# SubHarmonics_Main_Board_v2.net
KiCad netlist of a schematic drawn in EAGLE
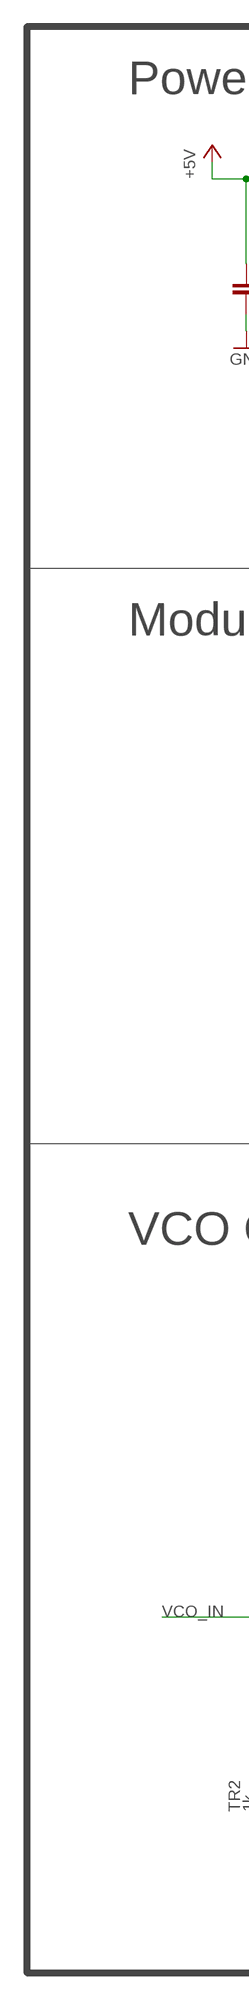
[diagram p0: schematic, sheet 1, part 1 of 2]
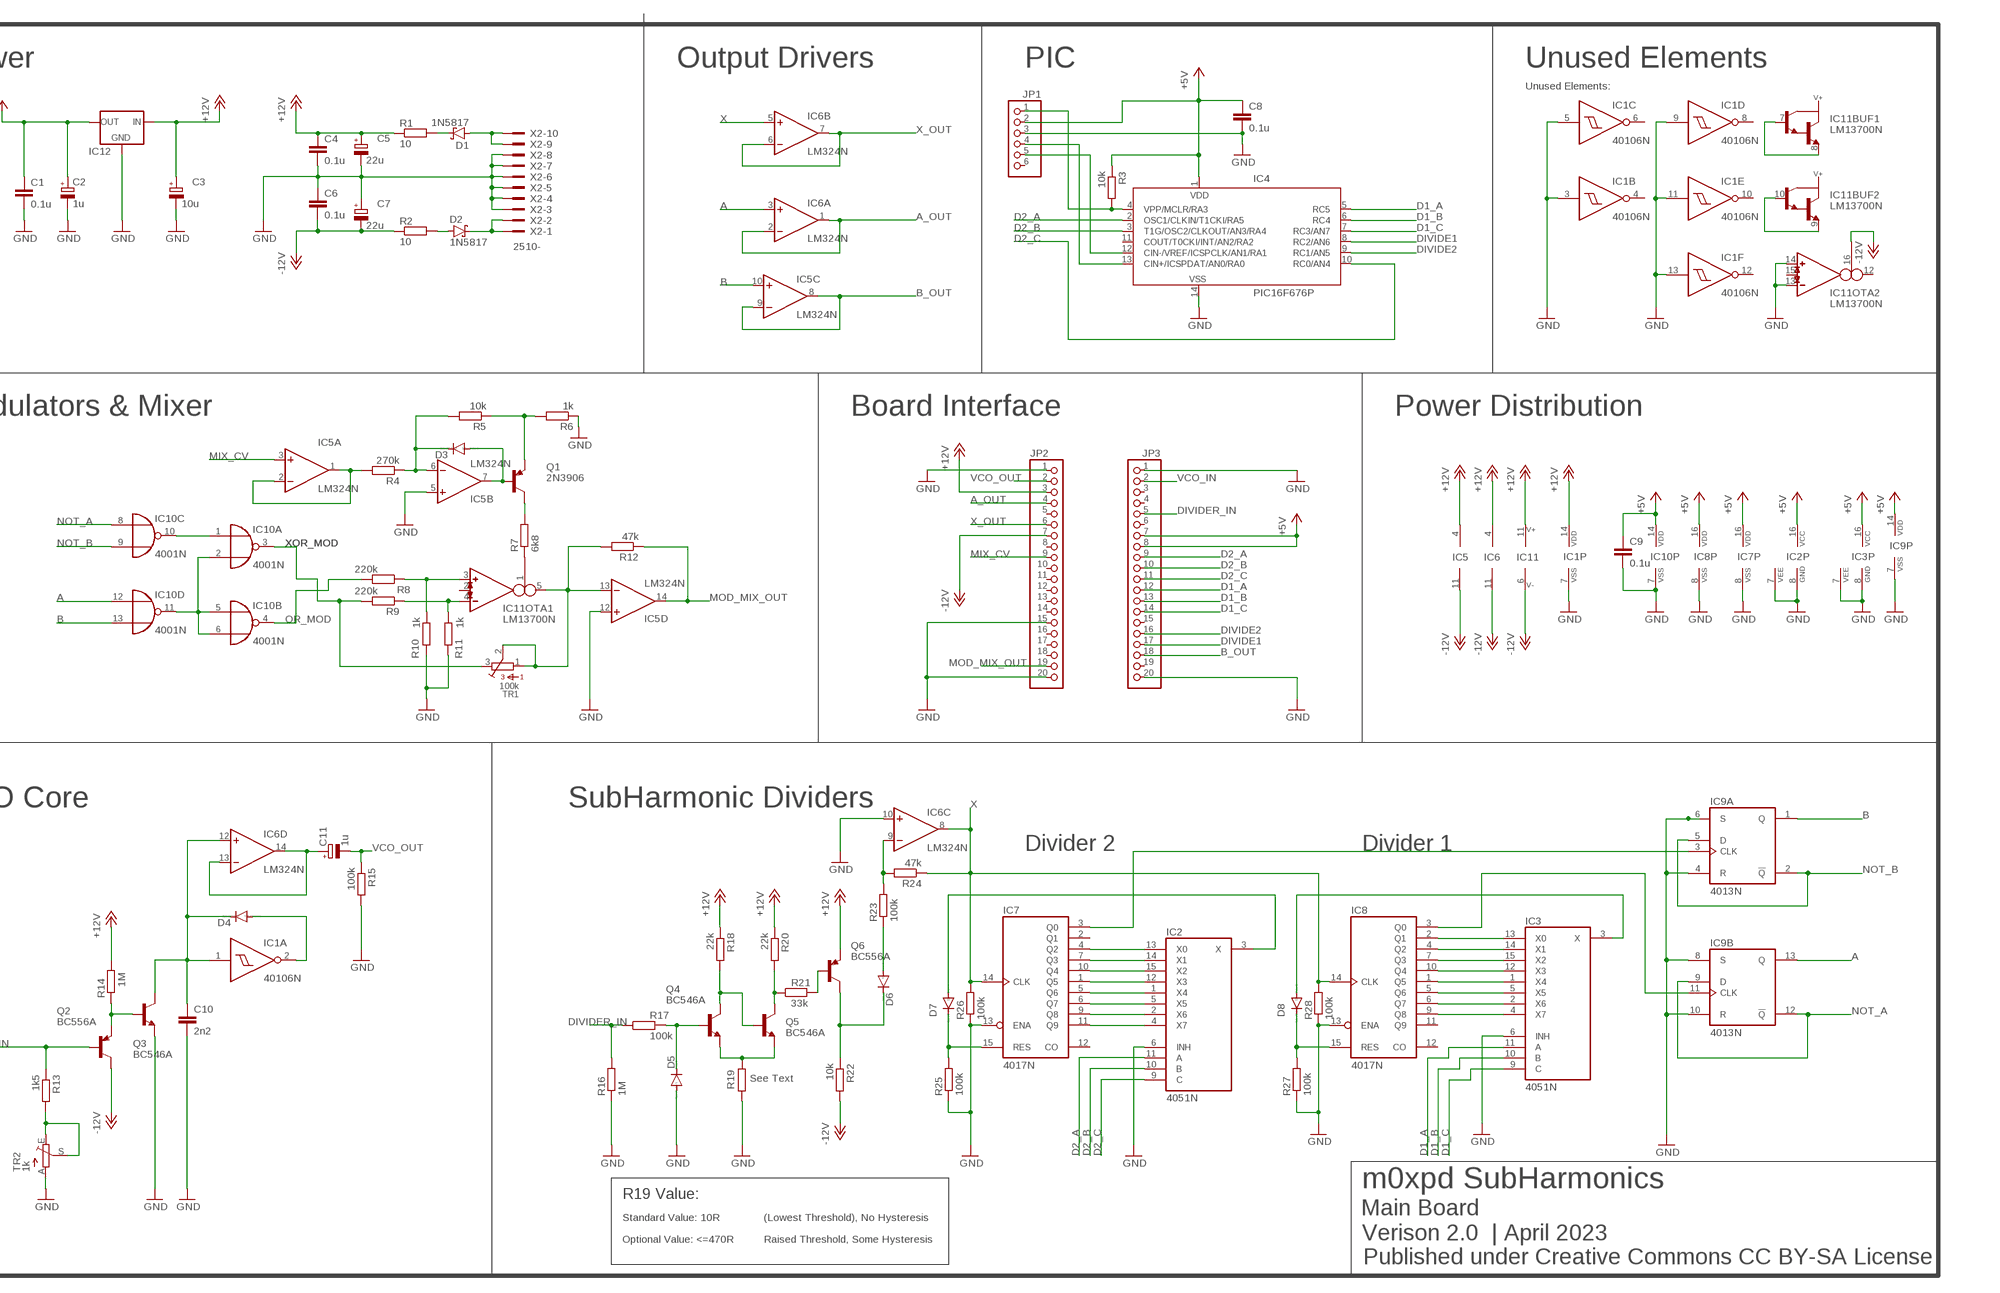
[diagram p1: schematic, sheet 1, part 2 of 2]

(export (version "E")
  (design (tool "Eeschema 10.0.6"))
  (components
    (comp (ref "C1")
      (value "0.1u")
      (footprint "eagle-import:C050-025X075")
      (libsource (lib "eagle-import") (part "C-EU050-025X075"))
    )
    (comp (ref "C2")
      (value "1u")
      (footprint "eagle-import:E2,5-5")
      (libsource (lib "eagle-import") (part "CPOL-EUE2.5-5"))
    )
    (comp (ref "C3")
      (value "10u")
      (footprint "eagle-import:E2,5-5")
      (libsource (lib "eagle-import") (part "CPOL-EUE2.5-5"))
    )
    (comp (ref "C4")
      (value "0.1u")
      (footprint "eagle-import:C050-025X075")
      (libsource (lib "eagle-import") (part "C-EU050-025X075"))
    )
    (comp (ref "C5")
      (value "22u")
      (footprint "eagle-import:E2,5-5")
      (libsource (lib "eagle-import") (part "CPOL-EUE2.5-5"))
    )
    (comp (ref "C6")
      (value "0.1u")
      (footprint "eagle-import:C050-025X075")
      (libsource (lib "eagle-import") (part "C-EU050-025X075"))
    )
    (comp (ref "C7")
      (value "22u")
      (footprint "eagle-import:E2,5-5")
      (libsource (lib "eagle-import") (part "CPOL-EUE2.5-5"))
    )
    (comp (ref "C8")
      (value "0.1u")
      (footprint "eagle-import:C050-025X075")
      (libsource (lib "eagle-import") (part "C-EU050-025X075"))
    )
    (comp (ref "C9")
      (value "0.1u")
      (footprint "eagle-import:C050-025X075")
      (libsource (lib "eagle-import") (part "C-EU050-025X075"))
    )
    (comp (ref "C10")
      (value "2n2")
      (footprint "eagle-import:C050-030X075")
      (libsource (lib "eagle-import") (part "C-EU050-030X075"))
    )
    (comp (ref "C11")
      (value "1u")
      (footprint "eagle-import:E2,5-5")
      (libsource (lib "eagle-import") (part "CPOL-EUE2.5-5"))
    )
    (comp (ref "D1")
      (value "1N5817")
      (footprint "eagle-import:DO35-7")
      (libsource (lib "eagle-import") (part "SCHOTTKY-DIODEDO35-7"))
    )
    (comp (ref "D2")
      (value "1N5817")
      (footprint "eagle-import:DO35-7")
      (libsource (lib "eagle-import") (part "SCHOTTKY-DIODEDO35-7"))
    )
    (comp (ref "D3")
      (value "1N4148DO35-7")
      (footprint "eagle-import:DO35-7")
      (libsource (lib "eagle-import") (part "1N4148DO35-7"))
    )
    (comp (ref "D4")
      (value "1N4148DO35-7")
      (footprint "eagle-import:DO35-7")
      (libsource (lib "eagle-import") (part "1N4148DO35-7"))
    )
    (comp (ref "D5")
      (value "1N4148DO35-7")
      (footprint "eagle-import:DO35-7")
      (libsource (lib "eagle-import") (part "1N4148DO35-7"))
    )
    (comp (ref "D6")
      (value "1N4148DO35-7")
      (footprint "eagle-import:DO35-7")
      (libsource (lib "eagle-import") (part "1N4148DO35-7"))
    )
    (comp (ref "D7")
      (value "1N4148DO35-7")
      (footprint "eagle-import:DO35-7")
      (libsource (lib "eagle-import") (part "1N4148DO35-7"))
    )
    (comp (ref "D8")
      (value "1N4148DO35-7")
      (footprint "eagle-import:DO35-7")
      (libsource (lib "eagle-import") (part "1N4148DO35-7"))
    )
    (comp (ref "IC1")
      (value "40106N")
      (footprint "eagle-import:DIL14")
      (libsource (lib "eagle-import") (part "40106N"))
    )
    (comp (ref "IC2")
      (value "4051N")
      (footprint "eagle-import:DIL16")
      (libsource (lib "eagle-import") (part "4051N"))
    )
    (comp (ref "IC3")
      (value "4051N")
      (footprint "eagle-import:DIL16")
      (libsource (lib "eagle-import") (part "4051N"))
    )
    (comp (ref "IC4")
      (value "PIC16F676P")
      (footprint "eagle-import:DIL14")
      (fields (field (name "MF") "MICROCHIP") (field (name "MPN") "PIC16F676-I/P"))
      (libsource (lib "eagle-import") (part "PIC16F676P"))
    )
    (comp (ref "IC5")
      (value "LM324N")
      (footprint "eagle-import:DIL14")
      (libsource (lib "eagle-import") (part "LM324N"))
    )
    (comp (ref "IC6")
      (value "LM324N")
      (footprint "eagle-import:DIL14")
      (libsource (lib "eagle-import") (part "LM324N"))
    )
    (comp (ref "IC7")
      (value "4017N")
      (footprint "eagle-import:DIL16")
      (libsource (lib "eagle-import") (part "4017N"))
    )
    (comp (ref "IC8")
      (value "4017N")
      (footprint "eagle-import:DIL16")
      (libsource (lib "eagle-import") (part "4017N"))
    )
    (comp (ref "IC9")
      (value "4013N")
      (footprint "eagle-import:DIL14")
      (libsource (lib "eagle-import") (part "4013N"))
    )
    (comp (ref "IC10")
      (value "4001N")
      (footprint "eagle-import:DIL14")
      (libsource (lib "eagle-import") (part "4001N"))
    )
    (comp (ref "IC11")
      (value "LM13700N")
      (footprint "eagle-import:DIL16")
      (libsource (lib "eagle-import") (part "LM13700N"))
    )
    (comp (ref "IC12")
      (value "78LXX")
      (footprint "eagle-import:78LXX")
      (libsource (lib "eagle-import") (part "78LXX"))
    )
    (comp (ref "JP1")
      (value "PINHD-1X6")
      (footprint "eagle-import:1X06")
      (libsource (lib "eagle-import") (part "PINHD-1X6"))
    )
    (comp (ref "JP2")
      (value "PINHD-1X20")
      (footprint "eagle-import:1X20")
      (libsource (lib "eagle-import") (part "PINHD-1X20"))
    )
    (comp (ref "JP3")
      (value "PINHD-1X20")
      (footprint "eagle-import:1X20")
      (libsource (lib "eagle-import") (part "PINHD-1X20"))
    )
    (comp (ref "Q1")
      (value "2N3906")
      (footprint "eagle-import:TO92")
      (libsource (lib "eagle-import") (part "2N3906"))
    )
    (comp (ref "Q2")
      (value "BC556A")
      (footprint "eagle-import:TO92-EBC")
      (libsource (lib "eagle-import") (part "BC556A"))
    )
    (comp (ref "Q3")
      (value "BC546A")
      (footprint "eagle-import:TO92-EBC")
      (libsource (lib "eagle-import") (part "BC546A"))
    )
    (comp (ref "Q4")
      (value "BC546A")
      (footprint "eagle-import:TO92-EBC")
      (libsource (lib "eagle-import") (part "BC546A"))
    )
    (comp (ref "Q5")
      (value "BC546A")
      (footprint "eagle-import:TO92-EBC")
      (libsource (lib "eagle-import") (part "BC546A"))
    )
    (comp (ref "Q6")
      (value "BC556A")
      (footprint "eagle-import:TO92-EBC")
      (libsource (lib "eagle-import") (part "BC556"))
    )
    (comp (ref "R1")
      (value "10")
      (footprint "eagle-import:0204_7")
      (libsource (lib "eagle-import") (part "R-EU_0204/7"))
    )
    (comp (ref "R2")
      (value "10")
      (footprint "eagle-import:0204_7")
      (libsource (lib "eagle-import") (part "R-EU_0204/7"))
    )
    (comp (ref "R3")
      (value "10k")
      (footprint "eagle-import:0204_7")
      (libsource (lib "eagle-import") (part "R-EU_0204/7"))
    )
    (comp (ref "R4")
      (value "270k")
      (footprint "eagle-import:0204_7")
      (libsource (lib "eagle-import") (part "R-EU_0204/7"))
    )
    (comp (ref "R5")
      (value "10k")
      (footprint "eagle-import:0204_7")
      (libsource (lib "eagle-import") (part "R-EU_0204/7"))
    )
    (comp (ref "R6")
      (value "1k")
      (footprint "eagle-import:0204_7")
      (libsource (lib "eagle-import") (part "R-EU_0204/7"))
    )
    (comp (ref "R7")
      (value "6k8")
      (footprint "eagle-import:0204_7")
      (libsource (lib "eagle-import") (part "R-EU_0204/7"))
    )
    (comp (ref "R8")
      (value "220k")
      (footprint "eagle-import:0204_7")
      (libsource (lib "eagle-import") (part "R-EU_0204/7"))
    )
    (comp (ref "R9")
      (value "220k")
      (footprint "eagle-import:0204_7")
      (libsource (lib "eagle-import") (part "R-EU_0204/7"))
    )
    (comp (ref "R10")
      (value "1k")
      (footprint "eagle-import:0204_7")
      (libsource (lib "eagle-import") (part "R-EU_0204/7"))
    )
    (comp (ref "R11")
      (value "1k")
      (footprint "eagle-import:0204_7")
      (libsource (lib "eagle-import") (part "R-EU_0204/7"))
    )
    (comp (ref "R12")
      (value "47k")
      (footprint "eagle-import:0204_7")
      (libsource (lib "eagle-import") (part "R-EU_0204/7"))
    )
    (comp (ref "R13")
      (value "1k5")
      (footprint "eagle-import:0204_7")
      (libsource (lib "eagle-import") (part "R-EU_0204/7"))
    )
    (comp (ref "R14")
      (value "1M")
      (footprint "eagle-import:0204_7")
      (libsource (lib "eagle-import") (part "R-EU_0204/7"))
    )
    (comp (ref "R15")
      (value "100k")
      (footprint "eagle-import:0204_7")
      (libsource (lib "eagle-import") (part "R-EU_0204/7"))
    )
    (comp (ref "R16")
      (value "1M")
      (footprint "eagle-import:0204_7")
      (libsource (lib "eagle-import") (part "R-EU_0204/7"))
    )
    (comp (ref "R17")
      (value "100k")
      (footprint "eagle-import:0204_7")
      (libsource (lib "eagle-import") (part "R-EU_0204/7"))
    )
    (comp (ref "R18")
      (value "22k")
      (footprint "eagle-import:0204_7")
      (libsource (lib "eagle-import") (part "R-EU_0204/7"))
    )
    (comp (ref "R19")
      (value "See Text")
      (footprint "eagle-import:0204_7")
      (libsource (lib "eagle-import") (part "R-EU_0204/7"))
    )
    (comp (ref "R20")
      (value "22k")
      (footprint "eagle-import:0204_7")
      (libsource (lib "eagle-import") (part "R-EU_0204/7"))
    )
    (comp (ref "R21")
      (value "33k")
      (footprint "eagle-import:0204_7")
      (libsource (lib "eagle-import") (part "R-EU_0204/7"))
    )
    (comp (ref "R22")
      (value "10k")
      (footprint "eagle-import:0204_7")
      (libsource (lib "eagle-import") (part "R-EU_0204/7"))
    )
    (comp (ref "R23")
      (value "100k")
      (footprint "eagle-import:0204_7")
      (libsource (lib "eagle-import") (part "R-EU_0204/7"))
    )
    (comp (ref "R24")
      (value "47k")
      (footprint "eagle-import:0204_7")
      (libsource (lib "eagle-import") (part "R-EU_0204/7"))
    )
    (comp (ref "R25")
      (value "100k")
      (footprint "eagle-import:0204_7")
      (libsource (lib "eagle-import") (part "R-EU_0204/7"))
    )
    (comp (ref "R26")
      (value "100k")
      (footprint "eagle-import:0204_7")
      (libsource (lib "eagle-import") (part "R-EU_0204/7"))
    )
    (comp (ref "R27")
      (value "100k")
      (footprint "eagle-import:0204_7")
      (libsource (lib "eagle-import") (part "R-EU_0204/7"))
    )
    (comp (ref "R28")
      (value "100k")
      (footprint "eagle-import:0204_7")
      (libsource (lib "eagle-import") (part "R-EU_0204/7"))
    )
    (comp (ref "TR1")
      (value "100k")
      (footprint "eagle-import:BOURNS_3362P_TRIMMER")
      (libsource (lib "eagle-import") (part "BOURNS_3362P_TRIMMERP"))
    )
    (comp (ref "TR2")
      (value "1k")
      (footprint "eagle-import:B64Y")
      (libsource (lib "eagle-import") (part "TRIM_EU-B64Y"))
    )
    (comp (ref "X2")
      (value "2510-")
      (footprint "eagle-import:PAK100_2500-10")
      (fields (field (name "MF") "3M") (field (name "MPN") "2510-6002UB"))
      (libsource (lib "eagle-import") (part "2510-"))
    )
  )
  (nets
    (net (code "1") (name "+5V") (class "Default")
      (node (ref "C1") (pin "1") (pinfunction "1_1") (pintype "passive"))
      (node (ref "C2") (pin "+") (pinfunction "+_+") (pintype "passive"))
      (node (ref "C8") (pin "1") (pinfunction "1_1") (pintype "passive"))
      (node (ref "C9") (pin "1") (pinfunction "1_1") (pintype "passive"))
      (node (ref "IC10") (pin "14") (pinfunction "VDD_14") (pintype "power_in"))
      (node (ref "IC12") (pin "OUT") (pinfunction "OUT_OUT") (pintype "passive"))
      (node (ref "IC2") (pin "16") (pinfunction "VCC_16") (pintype "power_in"))
      (node (ref "IC3") (pin "16") (pinfunction "VCC_16") (pintype "power_in"))
      (node (ref "IC4") (pin "1") (pinfunction "VDD_1") (pintype "power_in"))
      (node (ref "IC7") (pin "16") (pinfunction "VDD_16") (pintype "power_in"))
      (node (ref "IC8") (pin "16") (pinfunction "VDD_16") (pintype "power_in"))
      (node (ref "IC9") (pin "14") (pinfunction "VDD_14") (pintype "power_in"))
      (node (ref "JP1") (pin "2") (pinfunction "2_2") (pintype "passive"))
      (node (ref "JP3") (pin "7") (pinfunction "7_7") (pintype "passive"))
      (node (ref "JP3") (pin "8") (pinfunction "8_8") (pintype "passive"))
      (node (ref "R3") (pin "1") (pinfunction "1_1") (pintype "passive"))
    )
    (net (code "2") (name "+12V") (class "Default")
      (node (ref "C3") (pin "+") (pinfunction "+_+") (pintype "passive"))
      (node (ref "C4") (pin "1") (pinfunction "1_1") (pintype "passive"))
      (node (ref "C5") (pin "+") (pinfunction "+_+") (pintype "passive"))
      (node (ref "IC1") (pin "14") (pinfunction "VDD_14") (pintype "power_in"))
      (node (ref "IC11") (pin "11") (pinfunction "V+_11") (pintype "power_in"))
      (node (ref "IC12") (pin "IN") (pinfunction "IN_IN") (pintype "input"))
      (node (ref "IC5") (pin "4") (pinfunction "V+_4") (pintype "power_in"))
      (node (ref "IC6") (pin "4") (pinfunction "V+_4") (pintype "power_in"))
      (node (ref "JP2") (pin "3") (pinfunction "3_3") (pintype "passive"))
      (node (ref "Q6") (pin "E") (pinfunction "E_E") (pintype "passive"))
      (node (ref "R1") (pin "1") (pinfunction "1_1") (pintype "passive"))
      (node (ref "R14") (pin "2") (pinfunction "2_2") (pintype "passive"))
      (node (ref "R18") (pin "1") (pinfunction "1_1") (pintype "passive"))
      (node (ref "R20") (pin "1") (pinfunction "1_1") (pintype "passive"))
    )
    (net (code "3") (name "-12V") (class "Default")
      (node (ref "C6") (pin "2") (pinfunction "2_2") (pintype "passive"))
      (node (ref "C7") (pin "-") (pinfunction "-_-") (pintype "passive"))
      (node (ref "IC11") (pin "16") (pinfunction "I_BIAS_16") (pintype "input"))
      (node (ref "IC11") (pin "6") (pinfunction "V-_6") (pintype "power_in"))
      (node (ref "IC5") (pin "11") (pinfunction "V-_11") (pintype "power_in"))
      (node (ref "IC6") (pin "11") (pinfunction "V-_11") (pintype "power_in"))
      (node (ref "JP2") (pin "7") (pinfunction "7_7") (pintype "passive"))
      (node (ref "Q2") (pin "C") (pinfunction "C_C") (pintype "passive"))
      (node (ref "R2") (pin "1") (pinfunction "1_1") (pintype "passive"))
      (node (ref "R22") (pin "2") (pinfunction "2_2") (pintype "passive"))
    )
    (net (code "4") (name "/A") (class "Default")
      (node (ref "IC10") (pin "12") (pinfunction "I0_12") (pintype "input"))
      (node (ref "IC6") (pin "3") (pinfunction "+IN_3") (pintype "input"))
      (node (ref "IC9") (pin "13") (pinfunction "Q_13") (pintype "output"))
    )
    (net (code "5") (name "/A_OUT") (class "Default")
      (node (ref "IC6") (pin "1") (pinfunction "OUT_1") (pintype "output"))
      (node (ref "IC6") (pin "2") (pinfunction "-IN_2") (pintype "input"))
      (node (ref "JP2") (pin "4") (pinfunction "4_4") (pintype "passive"))
    )
    (net (code "6") (name "/B") (class "Default")
      (node (ref "IC10") (pin "13") (pinfunction "I1_13") (pintype "input"))
      (node (ref "IC5") (pin "10") (pinfunction "+IN_10") (pintype "input"))
      (node (ref "IC9") (pin "1") (pinfunction "Q_1") (pintype "output"))
    )
    (net (code "7") (name "/B_OUT") (class "Default")
      (node (ref "IC5") (pin "8") (pinfunction "OUT_8") (pintype "output"))
      (node (ref "IC5") (pin "9") (pinfunction "-IN_9") (pintype "input"))
      (node (ref "JP3") (pin "18") (pinfunction "18_18") (pintype "passive"))
    )
    (net (code "8") (name "/D1_A") (class "Default")
      (node (ref "IC3") (pin "11") (pinfunction "A_11") (pintype "input"))
      (node (ref "IC4") (pin "5") (pinfunction "RC5_5") (pintype "bidirectional"))
      (node (ref "JP3") (pin "12") (pinfunction "12_12") (pintype "passive"))
    )
    (net (code "9") (name "/D1_B") (class "Default")
      (node (ref "IC3") (pin "10") (pinfunction "B_10") (pintype "input"))
      (node (ref "IC4") (pin "6") (pinfunction "RC4_6") (pintype "bidirectional"))
      (node (ref "JP3") (pin "13") (pinfunction "13_13") (pintype "passive"))
    )
    (net (code "10") (name "/D1_C") (class "Default")
      (node (ref "IC3") (pin "9") (pinfunction "C_9") (pintype "input"))
      (node (ref "IC4") (pin "7") (pinfunction "RC3/AN7_7") (pintype "bidirectional"))
      (node (ref "JP3") (pin "14") (pinfunction "14_14") (pintype "passive"))
    )
    (net (code "11") (name "/D2_A") (class "Default")
      (node (ref "IC2") (pin "11") (pinfunction "A_11") (pintype "input"))
      (node (ref "IC4") (pin "2") (pinfunction "OSC1/CLKIN/T1CKI/RA5_2") (pintype "bidirectional"))
      (node (ref "JP3") (pin "9") (pinfunction "9_9") (pintype "passive"))
    )
    (net (code "12") (name "/D2_B") (class "Default")
      (node (ref "IC2") (pin "10") (pinfunction "B_10") (pintype "input"))
      (node (ref "IC4") (pin "3") (pinfunction "T1G/OSC2/CLKOUT/AN3/RA4_3") (pintype "bidirectional"))
      (node (ref "JP3") (pin "10") (pinfunction "10_10") (pintype "passive"))
    )
    (net (code "13") (name "/D2_C") (class "Default")
      (node (ref "IC2") (pin "9") (pinfunction "C_9") (pintype "input"))
      (node (ref "IC4") (pin "10") (pinfunction "RC0/AN4_10") (pintype "bidirectional"))
      (node (ref "JP3") (pin "11") (pinfunction "11_11") (pintype "passive"))
    )
    (net (code "14") (name "/DIVIDE1") (class "Default")
      (node (ref "IC4") (pin "8") (pinfunction "RC2/AN6_8") (pintype "bidirectional"))
      (node (ref "JP3") (pin "17") (pinfunction "17_17") (pintype "passive"))
    )
    (net (code "15") (name "/DIVIDE2") (class "Default")
      (node (ref "IC4") (pin "9") (pinfunction "RC1/AN5_9") (pintype "bidirectional"))
      (node (ref "JP3") (pin "16") (pinfunction "16_16") (pintype "passive"))
    )
    (net (code "16") (name "/DIVIDER_IN") (class "Default")
      (node (ref "JP3") (pin "5") (pinfunction "5_5") (pintype "passive"))
      (node (ref "R16") (pin "2") (pinfunction "2_2") (pintype "passive"))
      (node (ref "R17") (pin "1") (pinfunction "1_1") (pintype "passive"))
    )
    (net (code "17") (name "/MIX_CV") (class "Default")
      (node (ref "IC5") (pin "3") (pinfunction "+IN_3") (pintype "input"))
      (node (ref "JP2") (pin "9") (pinfunction "9_9") (pintype "passive"))
    )
    (net (code "18") (name "/MOD_MIX_OUT") (class "Default")
      (node (ref "IC5") (pin "14") (pinfunction "OUT_14") (pintype "output"))
      (node (ref "JP2") (pin "19") (pinfunction "19_19") (pintype "passive"))
      (node (ref "R12") (pin "1") (pinfunction "1_1") (pintype "passive"))
    )
    (net (code "19") (name "/NOT_A") (class "Default")
      (node (ref "IC10") (pin "8") (pinfunction "I0_8") (pintype "input"))
      (node (ref "IC9") (pin "12") (pinfunction "~{Q}_12") (pintype "output"))
      (node (ref "IC9") (pin "9") (pinfunction "D_9") (pintype "input"))
    )
    (net (code "20") (name "/NOT_B") (class "Default")
      (node (ref "IC10") (pin "9") (pinfunction "I1_9") (pintype "input"))
      (node (ref "IC9") (pin "2") (pinfunction "~{Q}_2") (pintype "output"))
      (node (ref "IC9") (pin "5") (pinfunction "D_5") (pintype "input"))
    )
    (net (code "21") (name "/OR_MOD") (class "Default")
      (node (ref "IC10") (pin "4") (pinfunction "O_4") (pintype "output"))
      (node (ref "R8") (pin "2") (pinfunction "2_2") (pintype "passive"))
    )
    (net (code "22") (name "/VCO_IN") (class "Default")
      (node (ref "JP3") (pin "2") (pinfunction "2_2") (pintype "passive"))
      (node (ref "Q2") (pin "B") (pinfunction "B_B") (pintype "passive"))
      (node (ref "R13") (pin "1") (pinfunction "1_1") (pintype "passive"))
    )
    (net (code "23") (name "/VCO_OUT") (class "Default")
      (node (ref "C11") (pin "-") (pinfunction "-_-") (pintype "passive"))
      (node (ref "JP2") (pin "2") (pinfunction "2_2") (pintype "passive"))
      (node (ref "R15") (pin "1") (pinfunction "1_1") (pintype "passive"))
    )
    (net (code "24") (name "/X") (class "Default")
      (node (ref "IC6") (pin "5") (pinfunction "+IN_5") (pintype "input"))
      (node (ref "IC6") (pin "8") (pinfunction "OUT_8") (pintype "output"))
      (node (ref "IC7") (pin "14") (pinfunction "CLK_14") (pintype "input"))
      (node (ref "IC8") (pin "14") (pinfunction "CLK_14") (pintype "input"))
      (node (ref "R24") (pin "1") (pinfunction "1_1") (pintype "passive"))
      (node (ref "R26") (pin "2") (pinfunction "2_2") (pintype "passive"))
      (node (ref "R28") (pin "2") (pinfunction "2_2") (pintype "passive"))
    )
    (net (code "25") (name "/XOR_MOD") (class "Default")
      (node (ref "IC10") (pin "3") (pinfunction "O_3") (pintype "output"))
      (node (ref "R9") (pin "2") (pinfunction "2_2") (pintype "passive"))
      (node (ref "TR1") (pin "3") (pinfunction "3_3") (pintype "passive"))
    )
    (net (code "26") (name "/X_OUT") (class "Default")
      (node (ref "IC6") (pin "6") (pinfunction "-IN_6") (pintype "input"))
      (node (ref "IC6") (pin "7") (pinfunction "OUT_7") (pintype "output"))
      (node (ref "JP2") (pin "6") (pinfunction "6_6") (pintype "passive"))
    )
    (net (code "27") (name "GND") (class "Default")
      (node (ref "C1") (pin "2") (pinfunction "2_2") (pintype "passive"))
      (node (ref "C10") (pin "2") (pinfunction "2_2") (pintype "passive"))
      (node (ref "C2") (pin "-") (pinfunction "-_-") (pintype "passive"))
      (node (ref "C3") (pin "-") (pinfunction "-_-") (pintype "passive"))
      (node (ref "C4") (pin "2") (pinfunction "2_2") (pintype "passive"))
      (node (ref "C5") (pin "-") (pinfunction "-_-") (pintype "passive"))
      (node (ref "C6") (pin "1") (pinfunction "1_1") (pintype "passive"))
      (node (ref "C7") (pin "+") (pinfunction "+_+") (pintype "passive"))
      (node (ref "C8") (pin "2") (pinfunction "2_2") (pintype "passive"))
      (node (ref "C9") (pin "2") (pinfunction "2_2") (pintype "passive"))
      (node (ref "D5") (pin "A") (pinfunction "A_A") (pintype "passive"))
      (node (ref "IC1") (pin "11") (pinfunction "I_11") (pintype "input"))
      (node (ref "IC1") (pin "13") (pinfunction "I_13") (pintype "input"))
      (node (ref "IC1") (pin "3") (pinfunction "I_3") (pintype "input"))
      (node (ref "IC1") (pin "5") (pinfunction "I_5") (pintype "input"))
      (node (ref "IC1") (pin "7") (pinfunction "VSS_7") (pintype "power_in"))
      (node (ref "IC1") (pin "9") (pinfunction "I_9") (pintype "input"))
      (node (ref "IC10") (pin "7") (pinfunction "VSS_7") (pintype "power_in"))
      (node (ref "IC11") (pin "13") (pinfunction "IN_N_13") (pintype "input"))
      (node (ref "IC11") (pin "14") (pinfunction "IN_P_14") (pintype "input"))
      (node (ref "IC12") (pin "GND") (pinfunction "GND_GND") (pintype "input"))
      (node (ref "IC2") (pin "6") (pinfunction "INH_6") (pintype "input"))
      (node (ref "IC2") (pin "7") (pinfunction "VEE_7") (pintype "power_in"))
      (node (ref "IC2") (pin "8") (pinfunction "GND_8") (pintype "power_in"))
      (node (ref "IC3") (pin "6") (pinfunction "INH_6") (pintype "input"))
      (node (ref "IC3") (pin "7") (pinfunction "VEE_7") (pintype "power_in"))
      (node (ref "IC3") (pin "8") (pinfunction "GND_8") (pintype "power_in"))
      (node (ref "IC4") (pin "14") (pinfunction "VSS_14") (pintype "power_in"))
      (node (ref "IC5") (pin "12") (pinfunction "+IN_12") (pintype "input"))
      (node (ref "IC5") (pin "5") (pinfunction "+IN_5") (pintype "input"))
      (node (ref "IC6") (pin "10") (pinfunction "+IN_10") (pintype "input"))
      (node (ref "IC7") (pin "13") (pinfunction "ENA_13") (pintype "input"))
      (node (ref "IC7") (pin "8") (pinfunction "VSS_8") (pintype "power_in"))
      (node (ref "IC8") (pin "13") (pinfunction "ENA_13") (pintype "input"))
      (node (ref "IC8") (pin "8") (pinfunction "VSS_8") (pintype "power_in"))
      (node (ref "IC9") (pin "10") (pinfunction "R_10") (pintype "input"))
      (node (ref "IC9") (pin "4") (pinfunction "R_4") (pintype "input"))
      (node (ref "IC9") (pin "6") (pinfunction "S_6") (pintype "input"))
      (node (ref "IC9") (pin "7") (pinfunction "VSS_7") (pintype "power_in"))
      (node (ref "IC9") (pin "8") (pinfunction "S_8") (pintype "input"))
      (node (ref "JP1") (pin "3") (pinfunction "3_3") (pintype "passive"))
      (node (ref "JP2") (pin "1") (pinfunction "1_1") (pintype "passive"))
      (node (ref "JP2") (pin "15") (pinfunction "15_15") (pintype "passive"))
      (node (ref "JP2") (pin "20") (pinfunction "20_20") (pintype "passive"))
      (node (ref "JP3") (pin "1") (pinfunction "1_1") (pintype "passive"))
      (node (ref "JP3") (pin "20") (pinfunction "20_20") (pintype "passive"))
      (node (ref "Q3") (pin "E") (pinfunction "E_E") (pintype "passive"))
      (node (ref "R10") (pin "2") (pinfunction "2_2") (pintype "passive"))
      (node (ref "R11") (pin "2") (pinfunction "2_2") (pintype "passive"))
      (node (ref "R15") (pin "2") (pinfunction "2_2") (pintype "passive"))
      (node (ref "R16") (pin "1") (pinfunction "1_1") (pintype "passive"))
      (node (ref "R19") (pin "2") (pinfunction "2_2") (pintype "passive"))
      (node (ref "R25") (pin "1") (pinfunction "1_1") (pintype "passive"))
      (node (ref "R26") (pin "1") (pinfunction "1_1") (pintype "passive"))
      (node (ref "R27") (pin "1") (pinfunction "1_1") (pintype "passive"))
      (node (ref "R28") (pin "1") (pinfunction "1_1") (pintype "passive"))
      (node (ref "R6") (pin "1") (pinfunction "1_1") (pintype "passive"))
      (node (ref "TR2") (pin "A") (pinfunction "A_A") (pintype "passive"))
      (node (ref "X2") (pin "3") (pinfunction "KL_3") (pintype "passive"))
      (node (ref "X2") (pin "4") (pinfunction "KL_4") (pintype "passive"))
      (node (ref "X2") (pin "5") (pinfunction "KL_5") (pintype "passive"))
      (node (ref "X2") (pin "6") (pinfunction "KL_6") (pintype "passive"))
      (node (ref "X2") (pin "7") (pinfunction "KL_7") (pintype "passive"))
      (node (ref "X2") (pin "8") (pinfunction "KL_8") (pintype "passive"))
    )
    (net (code "28") (name "Net-(D1-PadC)") (class "Default")
      (node (ref "D1") (pin "C") (pinfunction "C_C") (pintype "passive"))
      (node (ref "R1") (pin "2") (pinfunction "2_2") (pintype "passive"))
    )
    (net (code "29") (name "Net-(D2-PadA)") (class "Default")
      (node (ref "D2") (pin "A") (pinfunction "A_A") (pintype "passive"))
      (node (ref "R2") (pin "2") (pinfunction "2_2") (pintype "passive"))
    )
    (net (code "30") (name "Net-(D5-PadC)") (class "Default")
      (node (ref "D5") (pin "C") (pinfunction "C_C") (pintype "passive"))
      (node (ref "Q4") (pin "B") (pinfunction "B_B") (pintype "passive"))
      (node (ref "R17") (pin "2") (pinfunction "2_2") (pintype "passive"))
    )
    (net (code "31") (name "Net-(D6-PadA)") (class "Default")
      (node (ref "D6") (pin "A") (pinfunction "A_A") (pintype "passive"))
      (node (ref "R23") (pin "1") (pinfunction "1_1") (pintype "passive"))
    )
    (net (code "32") (name "Net-(D6-PadC)") (class "Default")
      (node (ref "D6") (pin "C") (pinfunction "C_C") (pintype "passive"))
      (node (ref "Q6") (pin "C") (pinfunction "C_C") (pintype "passive"))
      (node (ref "R22") (pin "1") (pinfunction "1_1") (pintype "passive"))
    )
    (net (code "33") (name "Net-(IC1A-I)") (class "Default")
      (node (ref "C10") (pin "1") (pinfunction "1_1") (pintype "passive"))
      (node (ref "D4") (pin "C") (pinfunction "C_C") (pintype "passive"))
      (node (ref "IC1") (pin "1") (pinfunction "I_1") (pintype "input"))
      (node (ref "IC6") (pin "12") (pinfunction "+IN_12") (pintype "input"))
      (node (ref "Q3") (pin "C") (pinfunction "C_C") (pintype "passive"))
    )
    (net (code "34") (name "Net-(IC1A-O)") (class "Default")
      (node (ref "D4") (pin "A") (pinfunction "A_A") (pintype "passive"))
      (node (ref "IC1") (pin "2") (pinfunction "O_2") (pintype "output"))
    )
    (net (code "35") (name "Net-(IC2A-X)") (class "Default")
      (node (ref "D7") (pin "A") (pinfunction "A_A") (pintype "passive"))
      (node (ref "IC2") (pin "3") (pinfunction "X_3") (pintype "bidirectional"))
    )
    (net (code "36") (name "Net-(IC2A-X0)") (class "Default")
      (node (ref "IC2") (pin "13") (pinfunction "X0_13") (pintype "bidirectional"))
      (node (ref "IC7") (pin "4") (pinfunction "Q2_4") (pintype "output"))
    )
    (net (code "37") (name "Net-(IC2A-X1)") (class "Default")
      (node (ref "IC2") (pin "14") (pinfunction "X1_14") (pintype "bidirectional"))
      (node (ref "IC7") (pin "7") (pinfunction "Q3_7") (pintype "output"))
    )
    (net (code "38") (name "Net-(IC2A-X2)") (class "Default")
      (node (ref "IC2") (pin "15") (pinfunction "X2_15") (pintype "bidirectional"))
      (node (ref "IC7") (pin "10") (pinfunction "Q4_10") (pintype "output"))
    )
    (net (code "39") (name "Net-(IC2A-X3)") (class "Default")
      (node (ref "IC2") (pin "12") (pinfunction "X3_12") (pintype "bidirectional"))
      (node (ref "IC7") (pin "1") (pinfunction "Q5_1") (pintype "output"))
    )
    (net (code "40") (name "Net-(IC2A-X4)") (class "Default")
      (node (ref "IC2") (pin "1") (pinfunction "X4_1") (pintype "bidirectional"))
      (node (ref "IC7") (pin "5") (pinfunction "Q6_5") (pintype "output"))
    )
    (net (code "41") (name "Net-(IC2A-X5)") (class "Default")
      (node (ref "IC2") (pin "5") (pinfunction "X5_5") (pintype "bidirectional"))
      (node (ref "IC7") (pin "6") (pinfunction "Q7_6") (pintype "output"))
    )
    (net (code "42") (name "Net-(IC2A-X6)") (class "Default")
      (node (ref "IC2") (pin "2") (pinfunction "X6_2") (pintype "bidirectional"))
      (node (ref "IC7") (pin "9") (pinfunction "Q8_9") (pintype "output"))
    )
    (net (code "43") (name "Net-(IC2A-X7)") (class "Default")
      (node (ref "IC2") (pin "4") (pinfunction "X7_4") (pintype "bidirectional"))
      (node (ref "IC7") (pin "11") (pinfunction "Q9_11") (pintype "output"))
    )
    (net (code "44") (name "Net-(IC3A-X)") (class "Default")
      (node (ref "D8") (pin "A") (pinfunction "A_A") (pintype "passive"))
      (node (ref "IC3") (pin "3") (pinfunction "X_3") (pintype "bidirectional"))
    )
    (net (code "45") (name "Net-(IC3A-X0)") (class "Default")
      (node (ref "IC3") (pin "13") (pinfunction "X0_13") (pintype "bidirectional"))
      (node (ref "IC8") (pin "2") (pinfunction "Q1_2") (pintype "output"))
    )
    (net (code "46") (name "Net-(IC3A-X1)") (class "Default")
      (node (ref "IC3") (pin "14") (pinfunction "X1_14") (pintype "bidirectional"))
      (node (ref "IC8") (pin "4") (pinfunction "Q2_4") (pintype "output"))
    )
    (net (code "47") (name "Net-(IC3A-X2)") (class "Default")
      (node (ref "IC3") (pin "15") (pinfunction "X2_15") (pintype "bidirectional"))
      (node (ref "IC8") (pin "7") (pinfunction "Q3_7") (pintype "output"))
    )
    (net (code "48") (name "Net-(IC3A-X3)") (class "Default")
      (node (ref "IC3") (pin "12") (pinfunction "X3_12") (pintype "bidirectional"))
      (node (ref "IC8") (pin "10") (pinfunction "Q4_10") (pintype "output"))
    )
    (net (code "49") (name "Net-(IC3A-X4)") (class "Default")
      (node (ref "IC3") (pin "1") (pinfunction "X4_1") (pintype "bidirectional"))
      (node (ref "IC8") (pin "1") (pinfunction "Q5_1") (pintype "output"))
    )
    (net (code "50") (name "Net-(IC3A-X5)") (class "Default")
      (node (ref "IC3") (pin "5") (pinfunction "X5_5") (pintype "bidirectional"))
      (node (ref "IC8") (pin "5") (pinfunction "Q6_5") (pintype "output"))
    )
    (net (code "51") (name "Net-(IC3A-X6)") (class "Default")
      (node (ref "IC3") (pin "2") (pinfunction "X6_2") (pintype "bidirectional"))
      (node (ref "IC8") (pin "6") (pinfunction "Q7_6") (pintype "output"))
    )
    (net (code "52") (name "Net-(IC3A-X7)") (class "Default")
      (node (ref "IC3") (pin "4") (pinfunction "X7_4") (pintype "bidirectional"))
      (node (ref "IC8") (pin "9") (pinfunction "Q8_9") (pintype "output"))
    )
    (net (code "53") (name "Net-(IC4-CIN+{slash}ICSPDAT{slash}AN0{slash}RA0)") (class "Default")
      (node (ref "IC4") (pin "13") (pinfunction "CIN+/ICSPDAT/AN0/RA0_13") (pintype "bidirectional"))
      (node (ref "JP1") (pin "4") (pinfunction "4_4") (pintype "passive"))
    )
    (net (code "54") (name "Net-(IC4-CIN-{slash}VREF{slash}ICSPCLK{slash}AN1{slash}RA1)") (class "Default")
      (node (ref "IC4") (pin "12") (pinfunction "CIN-/VREF/ICSPCLK/AN1/RA1_12") (pintype "bidirectional"))
      (node (ref "JP1") (pin "5") (pinfunction "5_5") (pintype "passive"))
    )
    (net (code "55") (name "Net-(IC4-VPP{slash}MCLR{slash}RA3)") (class "Default")
      (node (ref "IC4") (pin "4") (pinfunction "VPP/MCLR/RA3_4") (pintype "input"))
      (node (ref "JP1") (pin "1") (pinfunction "1_1") (pintype "passive"))
      (node (ref "R3") (pin "2") (pinfunction "2_2") (pintype "passive"))
    )
    (net (code "56") (name "Net-(IC5A--IN)") (class "Default")
      (node (ref "IC5") (pin "1") (pinfunction "OUT_1") (pintype "output"))
      (node (ref "IC5") (pin "2") (pinfunction "-IN_2") (pintype "input"))
      (node (ref "R4") (pin "2") (pinfunction "2_2") (pintype "passive"))
    )
    (net (code "57") (name "Net-(IC5B--IN)") (class "Default")
      (node (ref "D3") (pin "C") (pinfunction "C_C") (pintype "passive"))
      (node (ref "IC5") (pin "6") (pinfunction "-IN_6") (pintype "input"))
      (node (ref "R4") (pin "1") (pinfunction "1_1") (pintype "passive"))
      (node (ref "R5") (pin "2") (pinfunction "2_2") (pintype "passive"))
    )
    (net (code "58") (name "Net-(IC5B-OUT)") (class "Default")
      (node (ref "D3") (pin "A") (pinfunction "A_A") (pintype "passive"))
      (node (ref "IC5") (pin "7") (pinfunction "OUT_7") (pintype "output"))
      (node (ref "Q1") (pin "2") (pinfunction "B_2") (pintype "passive"))
    )
    (net (code "59") (name "Net-(IC6C--IN)") (class "Default")
      (node (ref "IC6") (pin "9") (pinfunction "-IN_9") (pintype "input"))
      (node (ref "R23") (pin "2") (pinfunction "2_2") (pintype "passive"))
      (node (ref "R24") (pin "2") (pinfunction "2_2") (pintype "passive"))
    )
    (net (code "60") (name "Net-(IC6D--IN)") (class "Default")
      (node (ref "C11") (pin "+") (pinfunction "+_+") (pintype "passive"))
      (node (ref "IC6") (pin "13") (pinfunction "-IN_13") (pintype "input"))
      (node (ref "IC6") (pin "14") (pinfunction "OUT_14") (pintype "output"))
    )
    (net (code "61") (name "Net-(IC7A-Q0)") (class "Default")
      (node (ref "IC7") (pin "3") (pinfunction "Q0_3") (pintype "output"))
      (node (ref "IC9") (pin "3") (pinfunction "CLK_3") (pintype "input"))
    )
    (net (code "62") (name "Net-(IC7A-RES)") (class "Default")
      (node (ref "D7") (pin "C") (pinfunction "C_C") (pintype "passive"))
      (node (ref "IC7") (pin "15") (pinfunction "RES_15") (pintype "input"))
      (node (ref "R25") (pin "2") (pinfunction "2_2") (pintype "passive"))
    )
    (net (code "63") (name "Net-(IC8A-Q0)") (class "Default")
      (node (ref "IC8") (pin "3") (pinfunction "Q0_3") (pintype "output"))
      (node (ref "IC9") (pin "11") (pinfunction "CLK_11") (pintype "input"))
    )
    (net (code "64") (name "Net-(IC8A-RES)") (class "Default")
      (node (ref "D8") (pin "C") (pinfunction "C_C") (pintype "passive"))
      (node (ref "IC8") (pin "15") (pinfunction "RES_15") (pintype "input"))
      (node (ref "R27") (pin "2") (pinfunction "2_2") (pintype "passive"))
    )
    (net (code "65") (name "Net-(IC10A-I0)") (class "Default")
      (node (ref "IC10") (pin "1") (pinfunction "I0_1") (pintype "input"))
      (node (ref "IC10") (pin "10") (pinfunction "O_10") (pintype "output"))
    )
    (net (code "66") (name "Net-(IC10A-I1)") (class "Default")
      (node (ref "IC10") (pin "11") (pinfunction "O_11") (pintype "output"))
      (node (ref "IC10") (pin "2") (pinfunction "I1_2") (pintype "input"))
      (node (ref "IC10") (pin "5") (pinfunction "I0_5") (pintype "input"))
      (node (ref "IC10") (pin "6") (pinfunction "I1_6") (pintype "input"))
    )
    (net (code "67") (name "Net-(IC11A-B)") (class "Default")
      (node (ref "IC11") (pin "7") (pinfunction "B_7") (pintype "passive"))
      (node (ref "IC11") (pin "8") (pinfunction "E_8") (pintype "passive"))
    )
    (net (code "68") (name "Net-(IC11B-B)") (class "Default")
      (node (ref "IC11") (pin "10") (pinfunction "B_10") (pintype "passive"))
      (node (ref "IC11") (pin "9") (pinfunction "E_9") (pintype "passive"))
    )
    (net (code "69") (name "Net-(IC11C-IN_N)") (class "Default")
      (node (ref "IC11") (pin "4") (pinfunction "IN_N_4") (pintype "input"))
      (node (ref "R11") (pin "1") (pinfunction "1_1") (pintype "passive"))
      (node (ref "R9") (pin "1") (pinfunction "1_1") (pintype "passive"))
    )
    (net (code "70") (name "Net-(IC11C-IN_P)") (class "Default")
      (node (ref "IC11") (pin "3") (pinfunction "IN_P_3") (pintype "input"))
      (node (ref "R10") (pin "1") (pinfunction "1_1") (pintype "passive"))
      (node (ref "R8") (pin "1") (pinfunction "1_1") (pintype "passive"))
    )
    (net (code "71") (name "Net-(IC11C-I_BIAS)") (class "Default")
      (node (ref "IC11") (pin "1") (pinfunction "I_BIAS_1") (pintype "input"))
      (node (ref "R7") (pin "1") (pinfunction "1_1") (pintype "passive"))
    )
    (net (code "72") (name "Net-(IC11C-OUT)") (class "Default")
      (node (ref "IC11") (pin "5") (pinfunction "OUT_5") (pintype "output"))
      (node (ref "IC5") (pin "13") (pinfunction "-IN_13") (pintype "input"))
      (node (ref "R12") (pin "2") (pinfunction "2_2") (pintype "passive"))
      (node (ref "TR1") (pin "1") (pinfunction "1_1") (pintype "passive"))
      (node (ref "TR1") (pin "2") (pinfunction "2_2") (pintype "passive"))
    )
    (net (code "73") (name "Net-(Q1-C)") (class "Default")
      (node (ref "Q1") (pin "1") (pinfunction "C_1") (pintype "passive"))
      (node (ref "R7") (pin "2") (pinfunction "2_2") (pintype "passive"))
    )
    (net (code "74") (name "Net-(Q1-E)") (class "Default")
      (node (ref "Q1") (pin "3") (pinfunction "E_3") (pintype "passive"))
      (node (ref "R5") (pin "1") (pinfunction "1_1") (pintype "passive"))
      (node (ref "R6") (pin "2") (pinfunction "2_2") (pintype "passive"))
    )
    (net (code "75") (name "Net-(Q2-PadE)") (class "Default")
      (node (ref "Q2") (pin "E") (pinfunction "E_E") (pintype "passive"))
      (node (ref "Q3") (pin "B") (pinfunction "B_B") (pintype "passive"))
      (node (ref "R14") (pin "1") (pinfunction "1_1") (pintype "passive"))
    )
    (net (code "76") (name "Net-(Q4-PadC)") (class "Default")
      (node (ref "Q4") (pin "C") (pinfunction "C_C") (pintype "passive"))
      (node (ref "Q5") (pin "B") (pinfunction "B_B") (pintype "passive"))
      (node (ref "R18") (pin "2") (pinfunction "2_2") (pintype "passive"))
    )
    (net (code "77") (name "Net-(Q4-PadE)") (class "Default")
      (node (ref "Q4") (pin "E") (pinfunction "E_E") (pintype "passive"))
      (node (ref "Q5") (pin "E") (pinfunction "E_E") (pintype "passive"))
      (node (ref "R19") (pin "1") (pinfunction "1_1") (pintype "passive"))
    )
    (net (code "78") (name "Net-(Q5-PadC)") (class "Default")
      (node (ref "Q5") (pin "C") (pinfunction "C_C") (pintype "passive"))
      (node (ref "R20") (pin "2") (pinfunction "2_2") (pintype "passive"))
      (node (ref "R21") (pin "1") (pinfunction "1_1") (pintype "passive"))
    )
    (net (code "79") (name "Net-(Q6-PadB)") (class "Default")
      (node (ref "Q6") (pin "B") (pinfunction "B_B") (pintype "passive"))
      (node (ref "R21") (pin "2") (pinfunction "2_2") (pintype "passive"))
    )
    (net (code "80") (name "Net-(R13-Pad2)") (class "Default")
      (node (ref "R13") (pin "2") (pinfunction "2_2") (pintype "passive"))
      (node (ref "TR2") (pin "E") (pinfunction "E_E") (pintype "passive"))
      (node (ref "TR2") (pin "S") (pinfunction "S_S") (pintype "passive"))
    )
    (net (code "81") (name "Net-(X2A-KL)") (class "Default")
      (node (ref "D2") (pin "C") (pinfunction "C_C") (pintype "passive"))
      (node (ref "X2") (pin "1") (pinfunction "KL_1") (pintype "passive"))
      (node (ref "X2") (pin "2") (pinfunction "KL_2") (pintype "passive"))
    )
    (net (code "82") (name "Net-(X2B-KL)") (class "Default")
      (node (ref "D1") (pin "A") (pinfunction "A_A") (pintype "passive"))
      (node (ref "X2") (pin "10") (pinfunction "KL_10") (pintype "passive"))
      (node (ref "X2") (pin "9") (pinfunction "KL_9") (pintype "passive"))
    )
    (net (code "83") (name "unconnected-(IC1B-O-Pad4)") (class "Default")
      (node (ref "IC1") (pin "4") (pinfunction "O_4") (pintype "output"))
    )
    (net (code "84") (name "unconnected-(IC1C-O-Pad6)") (class "Default")
      (node (ref "IC1") (pin "6") (pinfunction "O_6") (pintype "output"))
    )
    (net (code "85") (name "unconnected-(IC1D-O-Pad8)") (class "Default")
      (node (ref "IC1") (pin "8") (pinfunction "O_8") (pintype "output"))
    )
    (net (code "86") (name "unconnected-(IC1E-O-Pad10)") (class "Default")
      (node (ref "IC1") (pin "10") (pinfunction "O_10") (pintype "output"))
    )
    (net (code "87") (name "unconnected-(IC1F-O-Pad12)") (class "Default")
      (node (ref "IC1") (pin "12") (pinfunction "O_12") (pintype "output"))
    )
    (net (code "88") (name "unconnected-(IC4-COUT{slash}T0CKI{slash}INT{slash}AN2{slash}RA2-Pad11)") (class "Default")
      (node (ref "IC4") (pin "11") (pinfunction "COUT/T0CKI/INT/AN2/RA2_11") (pintype "bidirectional"))
    )
    (net (code "89") (name "unconnected-(IC7A-CO-Pad12)") (class "Default")
      (node (ref "IC7") (pin "12") (pinfunction "CO_12") (pintype "output"))
    )
    (net (code "90") (name "unconnected-(IC7A-Q1-Pad2)") (class "Default")
      (node (ref "IC7") (pin "2") (pinfunction "Q1_2") (pintype "output"))
    )
    (net (code "91") (name "unconnected-(IC8A-CO-Pad12)") (class "Default")
      (node (ref "IC8") (pin "12") (pinfunction "CO_12") (pintype "output"))
    )
    (net (code "92") (name "unconnected-(IC8A-Q9-Pad11)") (class "Default")
      (node (ref "IC8") (pin "11") (pinfunction "Q9_11") (pintype "output"))
    )
    (net (code "93") (name "unconnected-(IC11C-I_DIODE-Pad2)") (class "Default")
      (node (ref "IC11") (pin "2") (pinfunction "I_DIODE_2") (pintype "input"))
    )
    (net (code "94") (name "unconnected-(IC11D-I_DIODE-Pad15)") (class "Default")
      (node (ref "IC11") (pin "15") (pinfunction "I_DIODE_15") (pintype "input"))
    )
    (net (code "95") (name "unconnected-(IC11D-OUT-Pad12)") (class "Default")
      (node (ref "IC11") (pin "12") (pinfunction "OUT_12") (pintype "output"))
    )
    (net (code "96") (name "unconnected-(JP1-Pad6)") (class "Default")
      (node (ref "JP1") (pin "6") (pinfunction "6_6") (pintype "passive"))
    )
    (net (code "97") (name "unconnected-(JP2-Pad5)") (class "Default")
      (node (ref "JP2") (pin "5") (pinfunction "5_5") (pintype "passive"))
    )
    (net (code "98") (name "unconnected-(JP2-Pad8)") (class "Default")
      (node (ref "JP2") (pin "8") (pinfunction "8_8") (pintype "passive"))
    )
    (net (code "99") (name "unconnected-(JP2-Pad10)") (class "Default")
      (node (ref "JP2") (pin "10") (pinfunction "10_10") (pintype "passive"))
    )
    (net (code "100") (name "unconnected-(JP2-Pad11)") (class "Default")
      (node (ref "JP2") (pin "11") (pinfunction "11_11") (pintype "passive"))
    )
    (net (code "101") (name "unconnected-(JP2-Pad12)") (class "Default")
      (node (ref "JP2") (pin "12") (pinfunction "12_12") (pintype "passive"))
    )
    (net (code "102") (name "unconnected-(JP2-Pad13)") (class "Default")
      (node (ref "JP2") (pin "13") (pinfunction "13_13") (pintype "passive"))
    )
    (net (code "103") (name "unconnected-(JP2-Pad14)") (class "Default")
      (node (ref "JP2") (pin "14") (pinfunction "14_14") (pintype "passive"))
    )
    (net (code "104") (name "unconnected-(JP2-Pad16)") (class "Default")
      (node (ref "JP2") (pin "16") (pinfunction "16_16") (pintype "passive"))
    )
    (net (code "105") (name "unconnected-(JP2-Pad17)") (class "Default")
      (node (ref "JP2") (pin "17") (pinfunction "17_17") (pintype "passive"))
    )
    (net (code "106") (name "unconnected-(JP2-Pad18)") (class "Default")
      (node (ref "JP2") (pin "18") (pinfunction "18_18") (pintype "passive"))
    )
    (net (code "107") (name "unconnected-(JP3-Pad3)") (class "Default")
      (node (ref "JP3") (pin "3") (pinfunction "3_3") (pintype "passive"))
    )
    (net (code "108") (name "unconnected-(JP3-Pad4)") (class "Default")
      (node (ref "JP3") (pin "4") (pinfunction "4_4") (pintype "passive"))
    )
    (net (code "109") (name "unconnected-(JP3-Pad6)") (class "Default")
      (node (ref "JP3") (pin "6") (pinfunction "6_6") (pintype "passive"))
    )
    (net (code "110") (name "unconnected-(JP3-Pad15)") (class "Default")
      (node (ref "JP3") (pin "15") (pinfunction "15_15") (pintype "passive"))
    )
    (net (code "111") (name "unconnected-(JP3-Pad19)") (class "Default")
      (node (ref "JP3") (pin "19") (pinfunction "19_19") (pintype "passive"))
    )
  )
)
